# eurodev.net
KiCad netlist of a schematic drawn in EAGLE
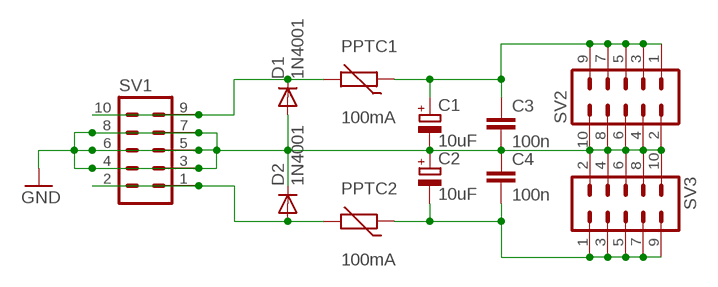
[diagram p0: schematic, sheet 1]

(export (version "E")
  (design (tool "Eeschema 10.0.6"))
  (components
    (comp (ref "C1")
      (value "10uF")
      (footprint "eagle-import:E2,5-6E")
      (fields (field (name "MF") "RUBYCON") (field (name "MPN") "35ZLG10MEFC5X7"))
      (libsource (lib "eagle-import") (part "CPOL-EUE2,5-6E"))
    )
    (comp (ref "C2")
      (value "10uF")
      (footprint "eagle-import:E2,5-6E")
      (fields (field (name "MF") "RUBYCON") (field (name "MPN") "35ZLG10MEFC5X7"))
      (libsource (lib "eagle-import") (part "CPOL-EUE2,5-6E"))
    )
    (comp (ref "C3")
      (value "100n")
      (footprint "eagle-import:C050-025X075")
      (fields (field (name "MF") "EPCOS") (field (name "MPN") "B32529C0104J289"))
      (libsource (lib "eagle-import") (part "C-EU050-025X075"))
    )
    (comp (ref "C4")
      (value "100n")
      (footprint "eagle-import:C050-025X075")
      (fields (field (name "MF") "EPCOS") (field (name "MPN") "B32529C0104J289"))
      (libsource (lib "eagle-import") (part "C-EU050-025X075"))
    )
    (comp (ref "D1")
      (value "1N4001")
      (footprint "eagle-import:DO41-10")
      (fields (field (name "MF") "VISHAY") (field (name "MPN") "1N4001-E3/54"))
      (libsource (lib "eagle-import") (part "1N4004"))
    )
    (comp (ref "D2")
      (value "1N4001")
      (footprint "eagle-import:DO41-10")
      (fields (field (name "MF") "VISHAY") (field (name "MPN") "1N4001-E3/54"))
      (libsource (lib "eagle-import") (part "1N4004"))
    )
    (comp (ref "PPTC1")
      (value "100mA")
      (footprint "eagle-import:R-5")
      (fields (field (name "MF") "LITTELFUSE") (field (name "MPN") "60R010XU"))
      (libsource (lib "eagle-import") (part "THERMISTOR-5"))
    )
    (comp (ref "PPTC2")
      (value "100mA")
      (footprint "eagle-import:R-5")
      (fields (field (name "MF") "LITTELFUSE") (field (name "MPN") "60R010XU"))
      (libsource (lib "eagle-import") (part "THERMISTOR-5"))
    )
    (comp (ref "SV1")
      (value "10_PIN_HEADER")
      (footprint "eagle-import:MA05-2")
      (fields
        (field (name "MF") "AMPHENOL ICC")
        (field (name "MPN") "67997-410HLF")
        (field (name "OC_FARNELL") "2751378")
      )
      (libsource (lib "eagle-import") (part "10_PIN_HEADER"))
    )
    (comp (ref "SV2")
      (value "MA05-2")
      (footprint "eagle-import:MA05-2")
      (fields
        (field (name "MF") "AMPHENOL ICC")
        (field (name "MPN") "67997-410HLF")
        (field (name "OC_FARNELL") "2751378")
      )
      (libsource (lib "eagle-import") (part "MA05-2"))
    )
    (comp (ref "SV3")
      (value "MA05-2")
      (footprint "eagle-import:MA05-2")
      (fields
        (field (name "MF") "AMPHENOL ICC")
        (field (name "MPN") "67997-410HLF")
        (field (name "OC_FARNELL") "2751378")
      )
      (libsource (lib "eagle-import") (part "MA05-2"))
    )
  )
  (nets
    (net (code "1") (name "GND") (class "Default")
      (node (ref "C1") (pin "-") (pinfunction "-_-") (pintype "passive"))
      (node (ref "C2") (pin "+") (pinfunction "+_+") (pintype "passive"))
      (node (ref "C3") (pin "2") (pinfunction "2_2") (pintype "passive"))
      (node (ref "C4") (pin "1") (pinfunction "1_1") (pintype "passive"))
      (node (ref "D1") (pin "A") (pinfunction "A_A") (pintype "passive"))
      (node (ref "D2") (pin "C") (pinfunction "C_C") (pintype "passive"))
      (node (ref "SV1") (pin "3") (pinfunction "3_3") (pintype "passive"))
      (node (ref "SV1") (pin "4") (pinfunction "4_4") (pintype "passive"))
      (node (ref "SV1") (pin "5") (pinfunction "5_5") (pintype "passive"))
      (node (ref "SV1") (pin "6") (pinfunction "6_6") (pintype "passive"))
      (node (ref "SV1") (pin "7") (pinfunction "7_7") (pintype "passive"))
      (node (ref "SV1") (pin "8") (pinfunction "8_8") (pintype "passive"))
      (node (ref "SV2") (pin "10") (pinfunction "10_10") (pintype "passive"))
      (node (ref "SV2") (pin "2") (pinfunction "2_2") (pintype "passive"))
      (node (ref "SV2") (pin "4") (pinfunction "4_4") (pintype "passive"))
      (node (ref "SV2") (pin "6") (pinfunction "6_6") (pintype "passive"))
      (node (ref "SV2") (pin "8") (pinfunction "8_8") (pintype "passive"))
      (node (ref "SV3") (pin "10") (pinfunction "10_10") (pintype "passive"))
      (node (ref "SV3") (pin "2") (pinfunction "2_2") (pintype "passive"))
      (node (ref "SV3") (pin "4") (pinfunction "4_4") (pintype "passive"))
      (node (ref "SV3") (pin "6") (pinfunction "6_6") (pintype "passive"))
      (node (ref "SV3") (pin "8") (pinfunction "8_8") (pintype "passive"))
    )
    (net (code "2") (name "Net-(C1-Pad+)") (class "Default")
      (node (ref "C1") (pin "+") (pinfunction "+_+") (pintype "passive"))
      (node (ref "C3") (pin "1") (pinfunction "1_1") (pintype "passive"))
      (node (ref "PPTC1") (pin "1") (pinfunction "1_1") (pintype "passive"))
      (node (ref "SV2") (pin "1") (pinfunction "1_1") (pintype "passive"))
      (node (ref "SV2") (pin "3") (pinfunction "3_3") (pintype "passive"))
      (node (ref "SV2") (pin "5") (pinfunction "5_5") (pintype "passive"))
      (node (ref "SV2") (pin "7") (pinfunction "7_7") (pintype "passive"))
      (node (ref "SV2") (pin "9") (pinfunction "9_9") (pintype "passive"))
    )
    (net (code "3") (name "Net-(C2-Pad-)") (class "Default")
      (node (ref "C2") (pin "-") (pinfunction "-_-") (pintype "passive"))
      (node (ref "C4") (pin "2") (pinfunction "2_2") (pintype "passive"))
      (node (ref "PPTC2") (pin "1") (pinfunction "1_1") (pintype "passive"))
      (node (ref "SV3") (pin "1") (pinfunction "1_1") (pintype "passive"))
      (node (ref "SV3") (pin "3") (pinfunction "3_3") (pintype "passive"))
      (node (ref "SV3") (pin "5") (pinfunction "5_5") (pintype "passive"))
      (node (ref "SV3") (pin "7") (pinfunction "7_7") (pintype "passive"))
      (node (ref "SV3") (pin "9") (pinfunction "9_9") (pintype "passive"))
    )
    (net (code "4") (name "Net-(D1-PadC)") (class "Default")
      (node (ref "D1") (pin "C") (pinfunction "C_C") (pintype "passive"))
      (node (ref "PPTC1") (pin "2") (pinfunction "2_2") (pintype "passive"))
      (node (ref "SV1") (pin "10") (pinfunction "10_10") (pintype "passive"))
      (node (ref "SV1") (pin "9") (pinfunction "9_9") (pintype "passive"))
    )
    (net (code "5") (name "Net-(D2-PadA)") (class "Default")
      (node (ref "D2") (pin "A") (pinfunction "A_A") (pintype "passive"))
      (node (ref "PPTC2") (pin "2") (pinfunction "2_2") (pintype "passive"))
      (node (ref "SV1") (pin "1") (pinfunction "1_1") (pintype "passive"))
      (node (ref "SV1") (pin "2") (pinfunction "2_2") (pintype "passive"))
    )
  )
)
